# frontend_v2.net
KiCad netlist of a schematic drawn in EAGLE
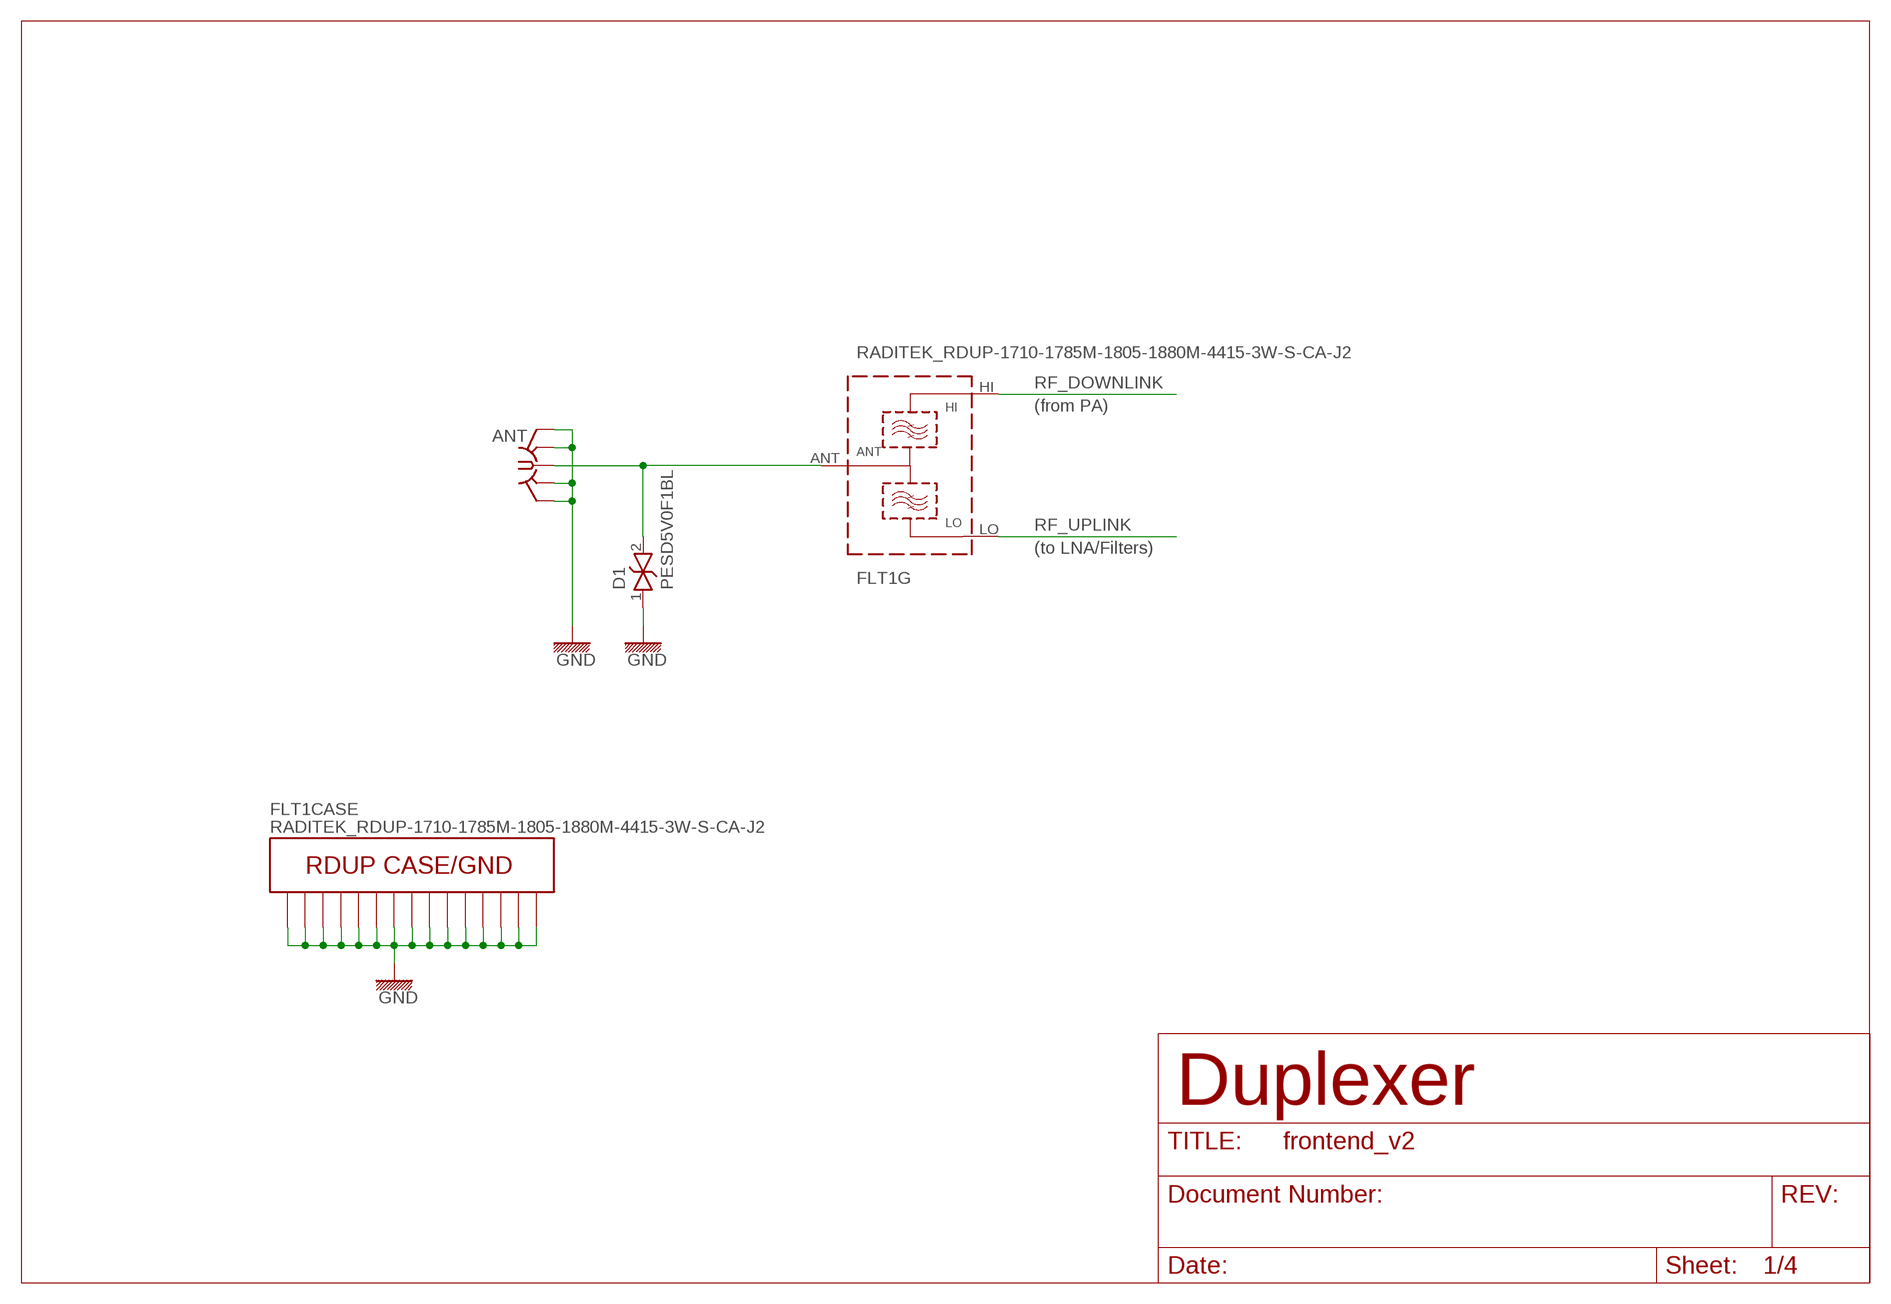
[diagram p0: schematic, sheet 1]
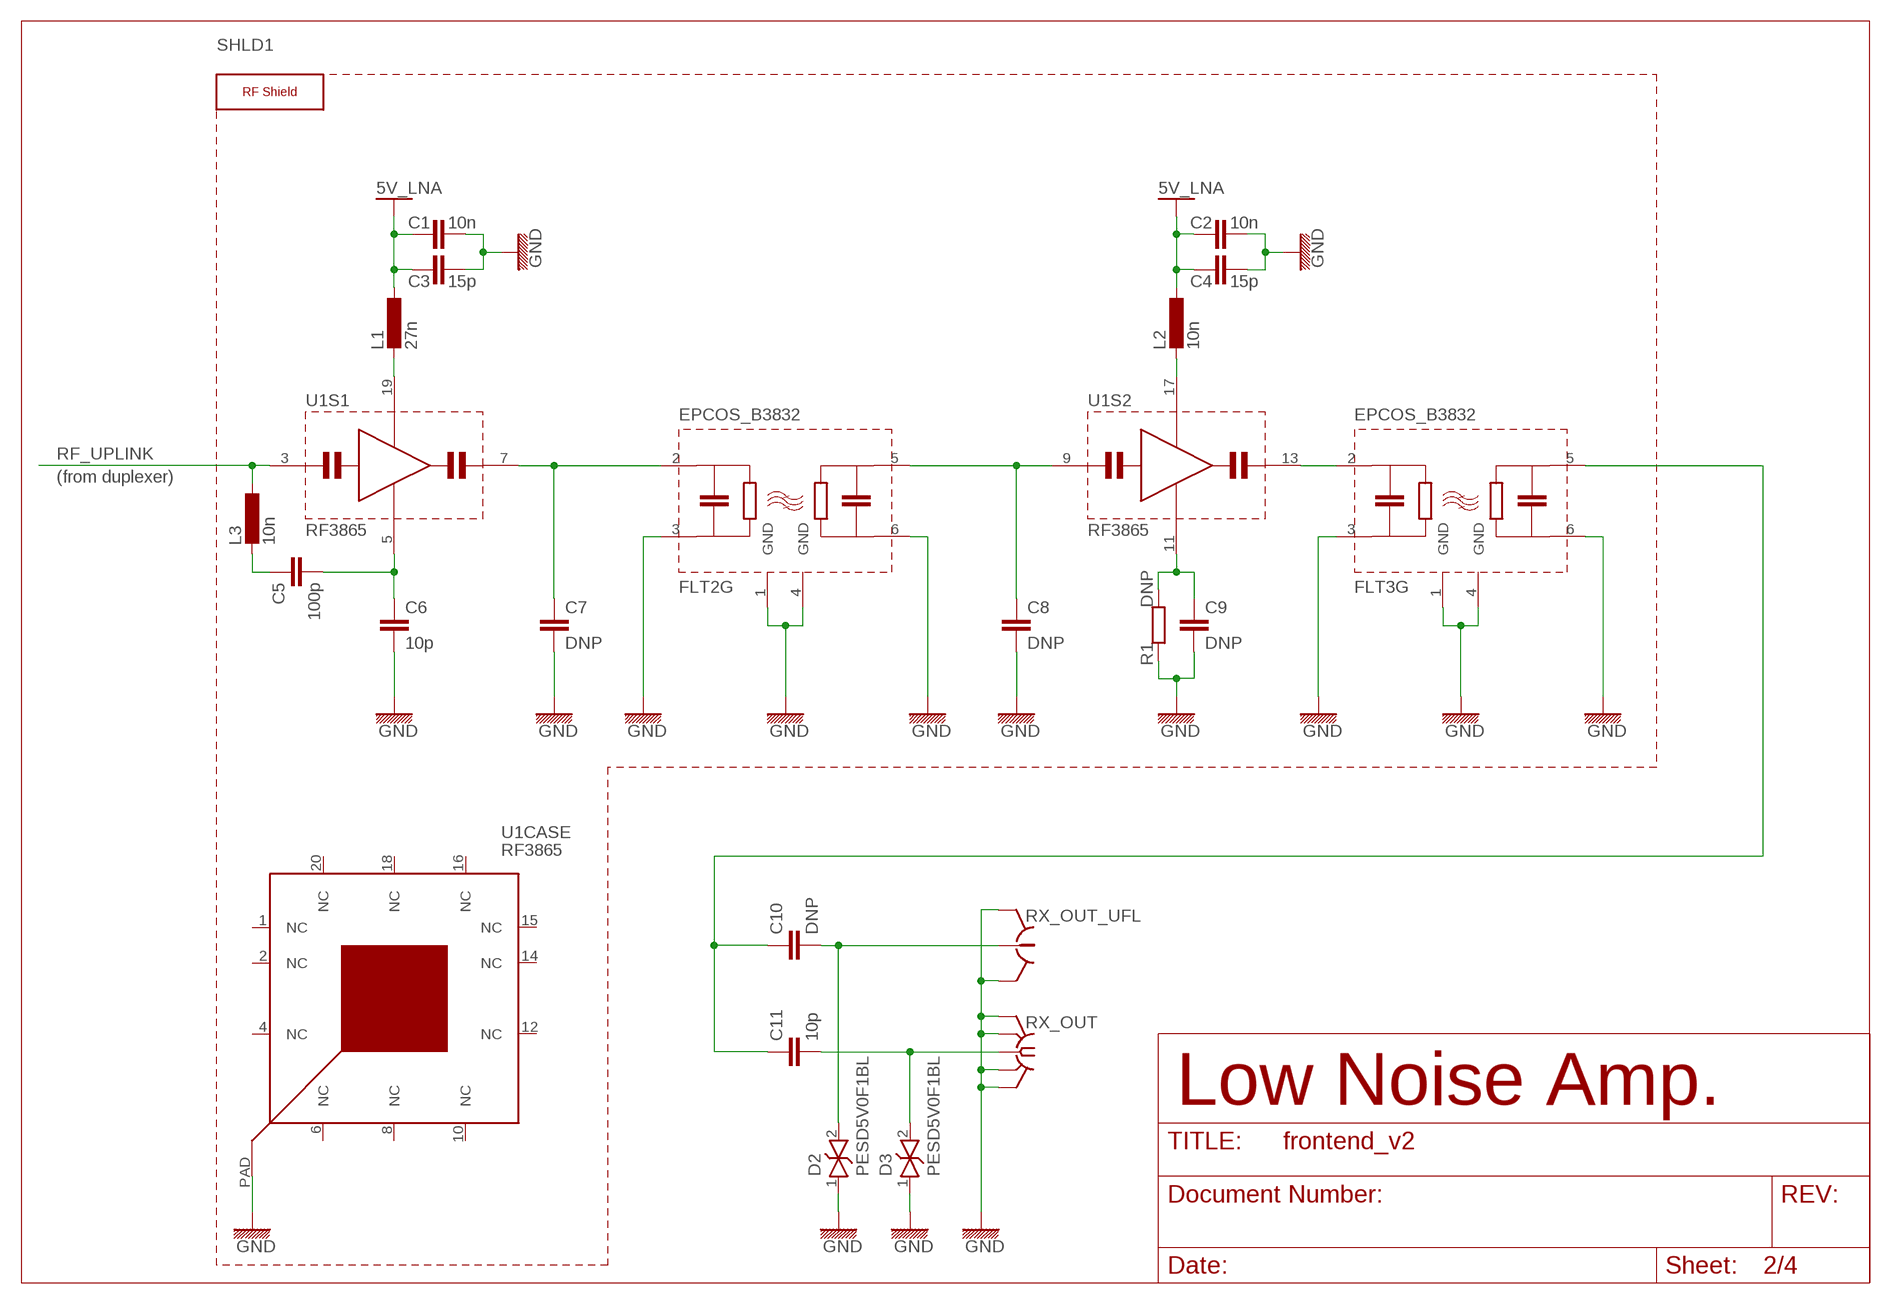
[diagram p1: schematic, sheet 2]
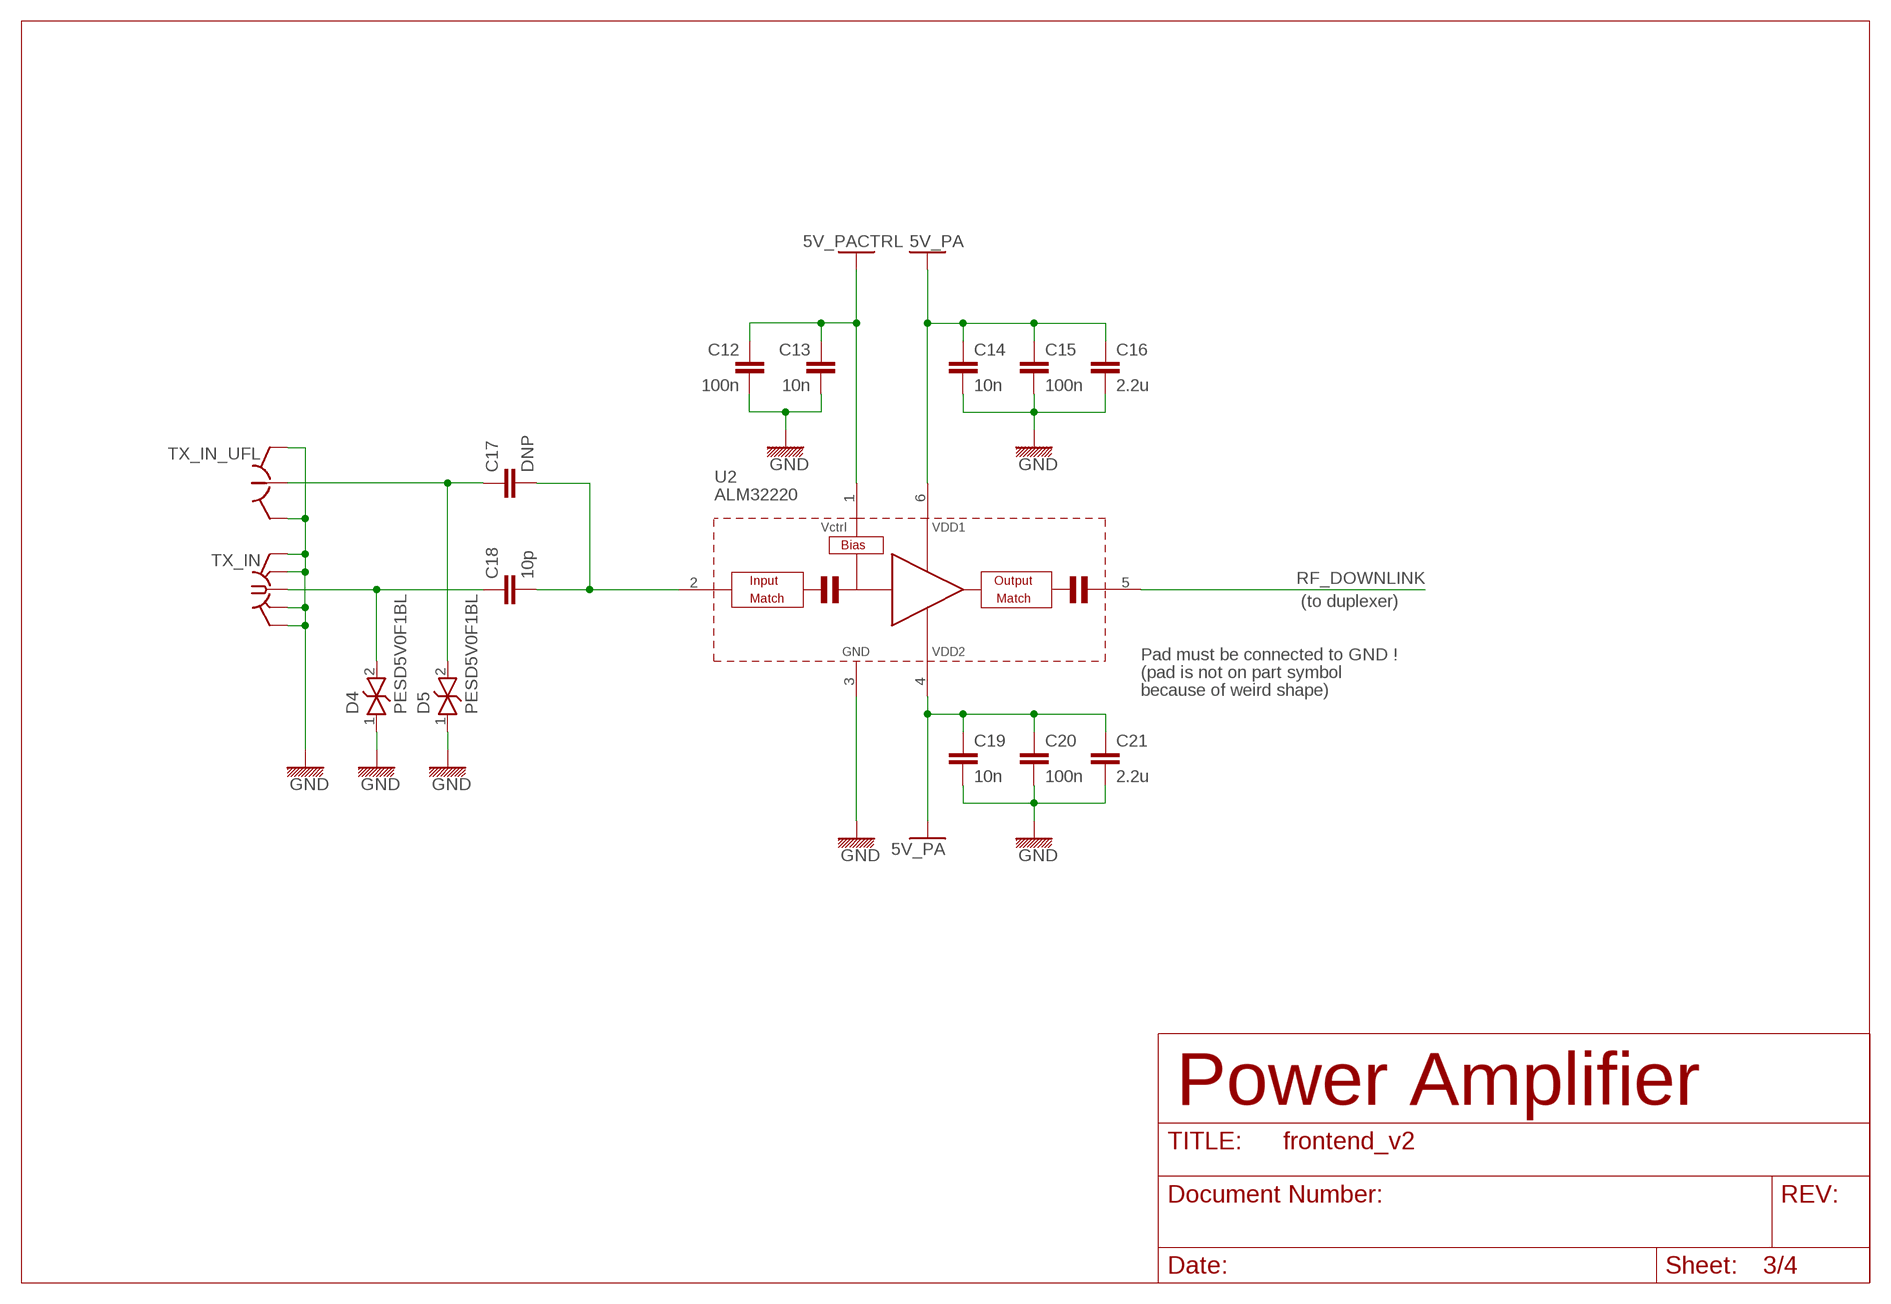
[diagram p2: schematic, sheet 3]
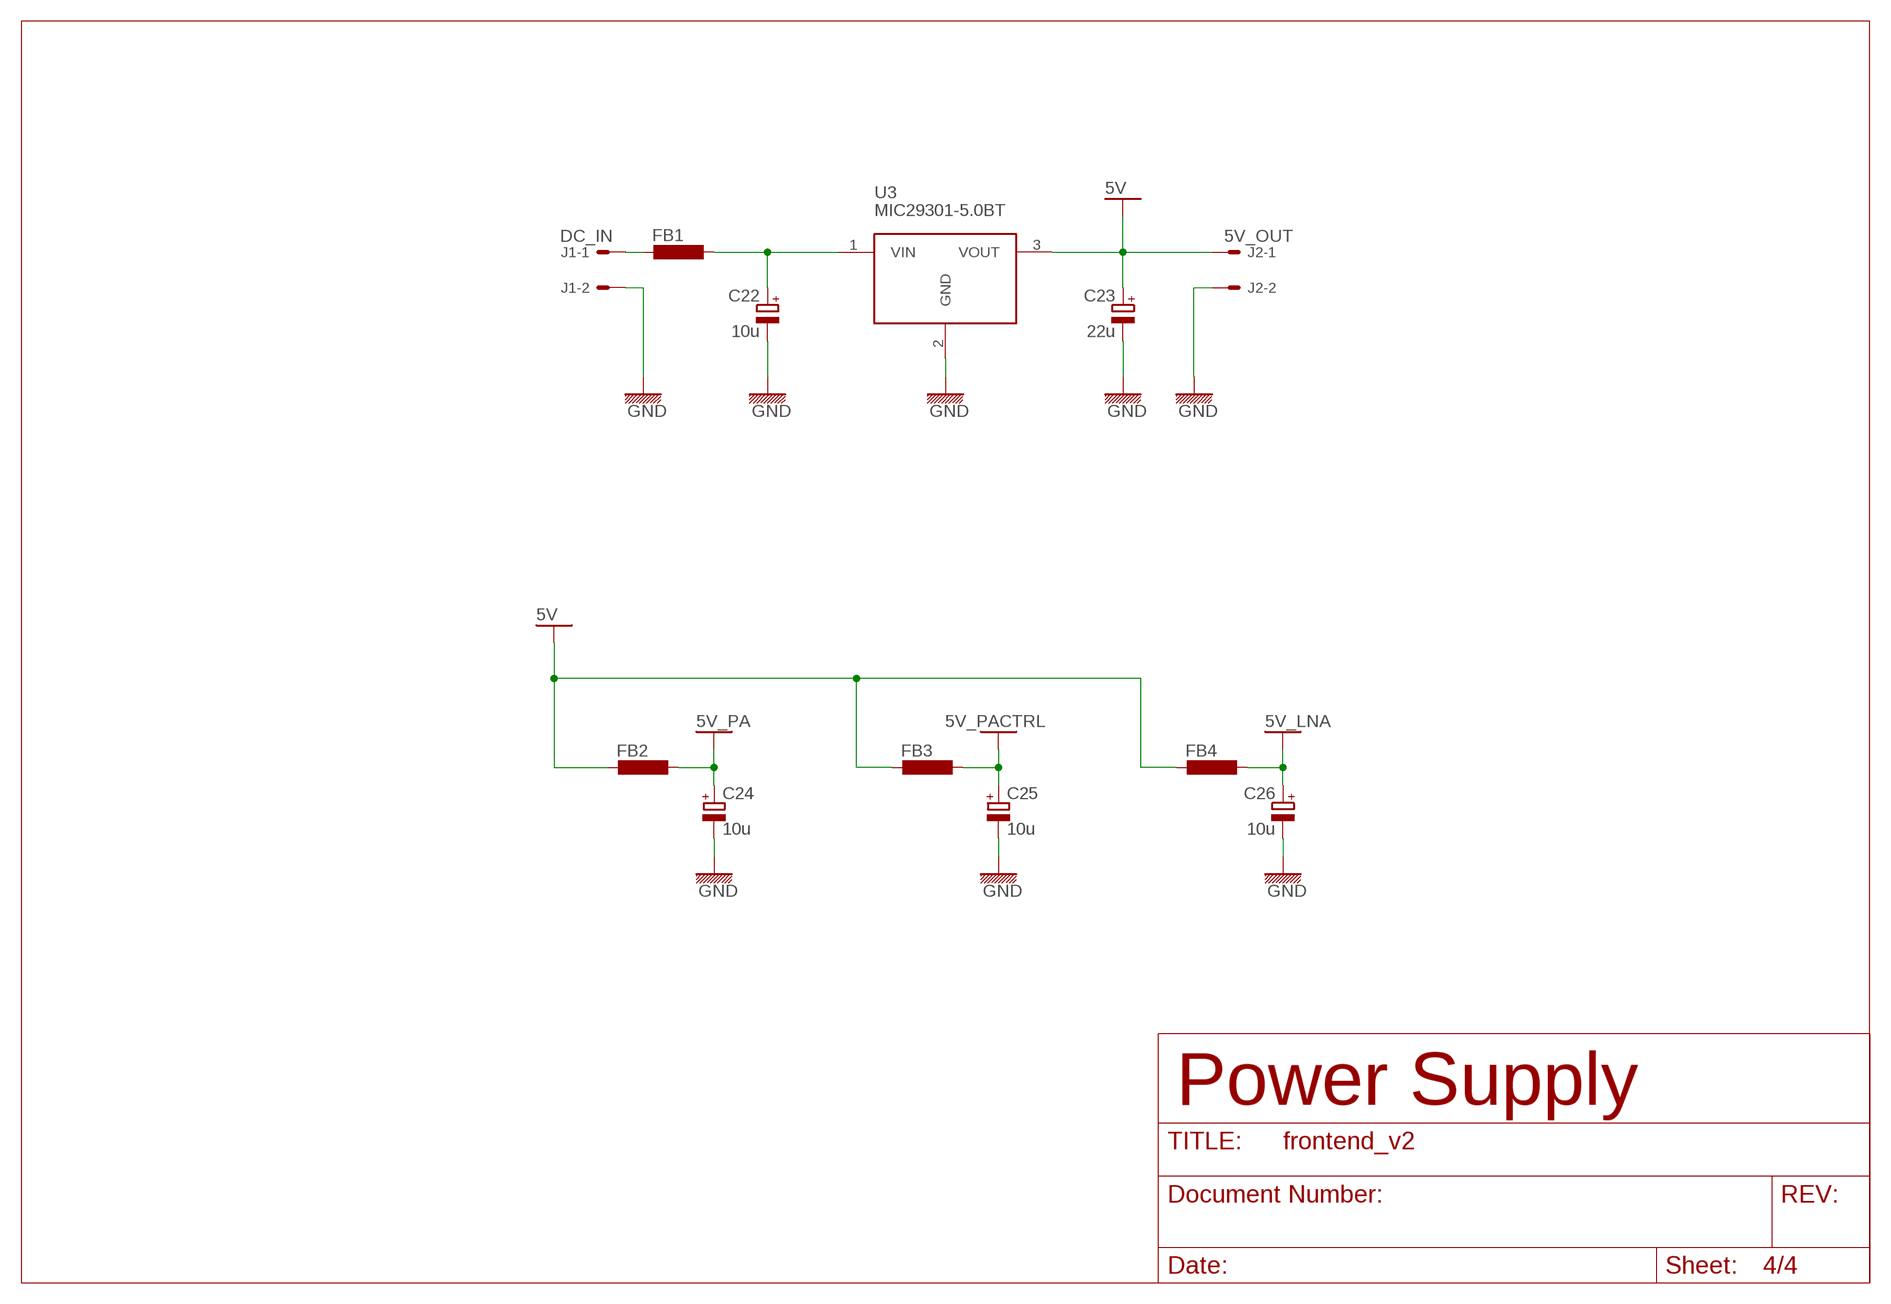
[diagram p3: schematic, sheet 4]

(export (version "E")
  (design (tool "Eeschema 10.0.6"))
  (components
    (comp (ref "C1")
      (value "10n")
      (footprint "eagle-import:0603")
      (libsource (lib "eagle-import") (part "C-EU_0603"))
    )
    (comp (ref "C2")
      (value "10n")
      (footprint "eagle-import:0603")
      (libsource (lib "eagle-import") (part "C-EU_0603"))
    )
    (comp (ref "C3")
      (value "15p")
      (footprint "eagle-import:0603")
      (libsource (lib "eagle-import") (part "C-EU_0603"))
    )
    (comp (ref "C4")
      (value "15p")
      (footprint "eagle-import:0603")
      (libsource (lib "eagle-import") (part "C-EU_0603"))
    )
    (comp (ref "C5")
      (value "100p")
      (footprint "eagle-import:0603")
      (libsource (lib "eagle-import") (part "C-EU_0603"))
    )
    (comp (ref "C6")
      (value "10p")
      (footprint "eagle-import:0603")
      (libsource (lib "eagle-import") (part "C-EU_0603"))
    )
    (comp (ref "C7")
      (value "DNP")
      (footprint "eagle-import:0603")
      (libsource (lib "eagle-import") (part "C-EU_0603"))
    )
    (comp (ref "C8")
      (value "DNP")
      (footprint "eagle-import:0603")
      (libsource (lib "eagle-import") (part "C-EU_0603"))
    )
    (comp (ref "C9")
      (value "DNP")
      (footprint "eagle-import:0603")
      (libsource (lib "eagle-import") (part "C-EU_0603"))
    )
    (comp (ref "C10")
      (value "DNP")
      (footprint "eagle-import:0603")
      (libsource (lib "eagle-import") (part "C-EU_0603"))
    )
    (comp (ref "C11")
      (value "10p")
      (footprint "eagle-import:0603")
      (libsource (lib "eagle-import") (part "C-EU_0603"))
    )
    (comp (ref "D2")
      (value "PESD5V0F1BL")
      (footprint "eagle-import:SOD882")
      (libsource (lib "eagle-import") (part "D_ESD_SOD882"))
    )
    (comp (ref "D3")
      (value "PESD5V0F1BL")
      (footprint "eagle-import:SOD882")
      (libsource (lib "eagle-import") (part "D_ESD_SOD882"))
    )
    (comp (ref "FLT2")
      (value "EPCOS_B3832")
      (footprint "eagle-import:DCC6C")
      (libsource (lib "eagle-import") (part "EPCOS_B3832"))
    )
    (comp (ref "FLT3")
      (value "EPCOS_B3832")
      (footprint "eagle-import:DCC6C")
      (libsource (lib "eagle-import") (part "EPCOS_B3832"))
    )
    (comp (ref "L1")
      (value "27n")
      (footprint "eagle-import:0603")
      (libsource (lib "eagle-import") (part "L-EU_0603"))
    )
    (comp (ref "L2")
      (value "10n")
      (footprint "eagle-import:0603")
      (libsource (lib "eagle-import") (part "L-EU_0603"))
    )
    (comp (ref "L3")
      (value "10n")
      (footprint "eagle-import:0603")
      (libsource (lib "eagle-import") (part "L-EU_0603"))
    )
    (comp (ref "R1")
      (value "DNP")
      (footprint "eagle-import:0603")
      (libsource (lib "eagle-import") (part "R-EU_0603"))
    )
    (comp (ref "RX_OUT")
      (value "SMA-F-S-TH")
      (footprint "eagle-import:SMA-F-S-TH")
      (libsource (lib "eagle-import") (part "SMA-F-S-TH"))
    )
    (comp (ref "RX_OUT_UFL")
      (value "HRS_UFL")
      (footprint "eagle-import:HRS_UFL")
      (libsource (lib "eagle-import") (part "HRS_UFL"))
    )
    (comp (ref "SHLD1")
      (value "SHIELD25X25")
      (footprint "eagle-import:WE-SHC-SMD_25X25")
      (libsource (lib "eagle-import") (part "SHIELD25X25"))
    )
    (comp (ref "U1")
      (value "RF3865")
      (footprint "eagle-import:QFN20_5X5_PAD")
      (libsource (lib "eagle-import") (part "RF3865"))
    )
    (comp (ref "C12")
      (value "100n")
      (footprint "eagle-import:0603")
      (libsource (lib "eagle-import") (part "C-EU_0603"))
    )
    (comp (ref "C13")
      (value "10n")
      (footprint "eagle-import:0603")
      (libsource (lib "eagle-import") (part "C-EU_0603"))
    )
    (comp (ref "C14")
      (value "10n")
      (footprint "eagle-import:0603")
      (libsource (lib "eagle-import") (part "C-EU_0603"))
    )
    (comp (ref "C15")
      (value "100n")
      (footprint "eagle-import:0603")
      (libsource (lib "eagle-import") (part "C-EU_0603"))
    )
    (comp (ref "C16")
      (value "2.2u")
      (footprint "eagle-import:0805")
      (libsource (lib "eagle-import") (part "C-EU_0805"))
    )
    (comp (ref "C17")
      (value "DNP")
      (footprint "eagle-import:0603")
      (libsource (lib "eagle-import") (part "C-EU_0603"))
    )
    (comp (ref "C18")
      (value "10p")
      (footprint "eagle-import:0603")
      (libsource (lib "eagle-import") (part "C-EU_0603"))
    )
    (comp (ref "C19")
      (value "10n")
      (footprint "eagle-import:0603")
      (libsource (lib "eagle-import") (part "C-EU_0603"))
    )
    (comp (ref "C20")
      (value "100n")
      (footprint "eagle-import:0603")
      (libsource (lib "eagle-import") (part "C-EU_0603"))
    )
    (comp (ref "C21")
      (value "2.2u")
      (footprint "eagle-import:0805")
      (libsource (lib "eagle-import") (part "C-EU_0805"))
    )
    (comp (ref "D4")
      (value "PESD5V0F1BL")
      (footprint "eagle-import:SOD882")
      (libsource (lib "eagle-import") (part "D_ESD_SOD882"))
    )
    (comp (ref "D5")
      (value "PESD5V0F1BL")
      (footprint "eagle-import:SOD882")
      (libsource (lib "eagle-import") (part "D_ESD_SOD882"))
    )
    (comp (ref "TX_IN")
      (value "SMA-F-S-TH")
      (footprint "eagle-import:SMA-F-S-TH")
      (libsource (lib "eagle-import") (part "SMA-F-S-TH"))
    )
    (comp (ref "TX_IN_UFL")
      (value "HRS_UFL")
      (footprint "eagle-import:HRS_UFL")
      (libsource (lib "eagle-import") (part "HRS_UFL"))
    )
    (comp (ref "U2")
      (value "ALM32220")
      (footprint "eagle-import:ALM32X20")
      (libsource (lib "eagle-import") (part "ALM32220"))
    )
    (comp (ref "C22")
      (value "10u")
      (footprint "eagle-import:SMC_A")
      (libsource (lib "eagle-import") (part "CPOL-EUSMCA"))
    )
    (comp (ref "C23")
      (value "22u")
      (footprint "eagle-import:SMC_A")
      (libsource (lib "eagle-import") (part "CPOL-EUSMCA"))
    )
    (comp (ref "C24")
      (value "10u")
      (footprint "eagle-import:SMC_A")
      (libsource (lib "eagle-import") (part "CPOL-EUSMCA"))
    )
    (comp (ref "C25")
      (value "10u")
      (footprint "eagle-import:SMC_A")
      (libsource (lib "eagle-import") (part "CPOL-EUSMCA"))
    )
    (comp (ref "C26")
      (value "10u")
      (footprint "eagle-import:SMC_A")
      (libsource (lib "eagle-import") (part "CPOL-EUSMCA"))
    )
    (comp (ref "FB1")
      (value "FBEAD_1206")
      (footprint "eagle-import:1206")
      (libsource (lib "eagle-import") (part "FBEAD_1206"))
    )
    (comp (ref "FB2")
      (value "FBEAD_1206")
      (footprint "eagle-import:1206")
      (libsource (lib "eagle-import") (part "FBEAD_1206"))
    )
    (comp (ref "FB3")
      (value "FBEAD_0603")
      (footprint "eagle-import:0603")
      (libsource (lib "eagle-import") (part "FBEAD_0603"))
    )
    (comp (ref "FB4")
      (value "FBEAD_0603")
      (footprint "eagle-import:0603")
      (libsource (lib "eagle-import") (part "FBEAD_0603"))
    )
    (comp (ref "J1")
      (value "DC_IN")
      (footprint "eagle-import:6410-02")
      (libsource (lib "eagle-import") (part "22-?-0227-2021"))
    )
    (comp (ref "J2")
      (value "5V_OUT")
      (footprint "eagle-import:6410-02")
      (fields (field (name "OC_FARNELL") "unknown") (field (name "OC_NEWARK") "unknown"))
      (libsource (lib "eagle-import") (part "22-?-0227-2021"))
    )
    (comp (ref "U3")
      (value "MIC29301-5.0BT")
      (footprint "eagle-import:TO220BV")
      (libsource (lib "eagle-import") (part "MIC29XXX-FIX_WT_TO220BV"))
    )
    (comp (ref "ANT")
      (value "SMA-F-S-TH")
      (footprint "eagle-import:SMA-F-S-TH")
      (libsource (lib "eagle-import") (part "SMA-F-S-TH"))
    )
    (comp (ref "D1")
      (value "PESD5V0F1BL")
      (footprint "eagle-import:SOD882")
      (libsource (lib "eagle-import") (part "D_ESD_SOD882"))
    )
    (comp (ref "FLT1")
      (value "RADITEK_RDUP-1710-1785M-1805-1880M-4415-3W-S-CA-J2")
      (footprint "eagle-import:RADITEK_RDUP_4415")
      (libsource (lib "eagle-import") (part "RADITEK_RDUP-1710-1785M-1805-1880M-4415-3W-S-CA-J2"))
    )
  )
  (nets
    (net (code "1") (name "5V") (class "Default")
      (node (ref "C23") (pin "+") (pinfunction "+_+") (pintype "passive"))
      (node (ref "FB2") (pin "1") (pinfunction "1_1") (pintype "passive"))
      (node (ref "FB3") (pin "1") (pinfunction "1_1") (pintype "passive"))
      (node (ref "FB4") (pin "1") (pinfunction "1_1") (pintype "passive"))
      (node (ref "J2") (pin "1") (pinfunction "S_1") (pintype "passive"))
      (node (ref "U3") (pin "3") (pinfunction "VOUT_3") (pintype "power_in"))
    )
    (net (code "2") (name "5V_LNA") (class "Default")
      (node (ref "C1") (pin "1") (pinfunction "1_1") (pintype "passive"))
      (node (ref "C2") (pin "1") (pinfunction "1_1") (pintype "passive"))
      (node (ref "C26") (pin "+") (pinfunction "+_+") (pintype "passive"))
      (node (ref "C3") (pin "1") (pinfunction "1_1") (pintype "passive"))
      (node (ref "C4") (pin "1") (pinfunction "1_1") (pintype "passive"))
      (node (ref "FB4") (pin "2") (pinfunction "2_2") (pintype "passive"))
      (node (ref "L1") (pin "1") (pinfunction "1_1") (pintype "passive"))
      (node (ref "L2") (pin "1") (pinfunction "1_1") (pintype "passive"))
    )
    (net (code "3") (name "5V_PA") (class "Default")
      (node (ref "C14") (pin "1") (pinfunction "1_1") (pintype "passive"))
      (node (ref "C15") (pin "1") (pinfunction "1_1") (pintype "passive"))
      (node (ref "C16") (pin "1") (pinfunction "1_1") (pintype "passive"))
      (node (ref "C19") (pin "1") (pinfunction "1_1") (pintype "passive"))
      (node (ref "C20") (pin "1") (pinfunction "1_1") (pintype "passive"))
      (node (ref "C21") (pin "1") (pinfunction "1_1") (pintype "passive"))
      (node (ref "C24") (pin "+") (pinfunction "+_+") (pintype "passive"))
      (node (ref "FB2") (pin "2") (pinfunction "2_2") (pintype "passive"))
      (node (ref "U2") (pin "4") (pinfunction "VDD2_4") (pintype "power_in"))
      (node (ref "U2") (pin "6") (pinfunction "VDD1_6") (pintype "power_in"))
    )
    (net (code "4") (name "5V_PACTRL") (class "Default")
      (node (ref "C12") (pin "1") (pinfunction "1_1") (pintype "passive"))
      (node (ref "C13") (pin "1") (pinfunction "1_1") (pintype "passive"))
      (node (ref "C25") (pin "+") (pinfunction "+_+") (pintype "passive"))
      (node (ref "FB3") (pin "2") (pinfunction "2_2") (pintype "passive"))
      (node (ref "U2") (pin "1") (pinfunction "VCTRL_1") (pintype "power_in"))
    )
    (net (code "5") (name "GND") (class "Default")
      (node (ref "ANT") (pin "G1") (pinfunction "GND_G1") (pintype "power_in"))
      (node (ref "ANT") (pin "G2") (pinfunction "GND_G2") (pintype "power_in"))
      (node (ref "ANT") (pin "G3") (pinfunction "GND_G3") (pintype "power_in"))
      (node (ref "ANT") (pin "G4") (pinfunction "GND_G4") (pintype "power_in"))
      (node (ref "C1") (pin "2") (pinfunction "2_2") (pintype "passive"))
      (node (ref "C12") (pin "2") (pinfunction "2_2") (pintype "passive"))
      (node (ref "C13") (pin "2") (pinfunction "2_2") (pintype "passive"))
      (node (ref "C14") (pin "2") (pinfunction "2_2") (pintype "passive"))
      (node (ref "C15") (pin "2") (pinfunction "2_2") (pintype "passive"))
      (node (ref "C16") (pin "2") (pinfunction "2_2") (pintype "passive"))
      (node (ref "C19") (pin "2") (pinfunction "2_2") (pintype "passive"))
      (node (ref "C2") (pin "2") (pinfunction "2_2") (pintype "passive"))
      (node (ref "C20") (pin "2") (pinfunction "2_2") (pintype "passive"))
      (node (ref "C21") (pin "2") (pinfunction "2_2") (pintype "passive"))
      (node (ref "C22") (pin "-") (pinfunction "-_-") (pintype "passive"))
      (node (ref "C23") (pin "-") (pinfunction "-_-") (pintype "passive"))
      (node (ref "C24") (pin "-") (pinfunction "-_-") (pintype "passive"))
      (node (ref "C25") (pin "-") (pinfunction "-_-") (pintype "passive"))
      (node (ref "C26") (pin "-") (pinfunction "-_-") (pintype "passive"))
      (node (ref "C3") (pin "2") (pinfunction "2_2") (pintype "passive"))
      (node (ref "C4") (pin "2") (pinfunction "2_2") (pintype "passive"))
      (node (ref "C6") (pin "2") (pinfunction "2_2") (pintype "passive"))
      (node (ref "C7") (pin "2") (pinfunction "2_2") (pintype "passive"))
      (node (ref "C8") (pin "2") (pinfunction "2_2") (pintype "passive"))
      (node (ref "C9") (pin "2") (pinfunction "2_2") (pintype "passive"))
      (node (ref "D1") (pin "1") (pinfunction "1_1") (pintype "passive"))
      (node (ref "D2") (pin "1") (pinfunction "1_1") (pintype "passive"))
      (node (ref "D3") (pin "1") (pinfunction "1_1") (pintype "passive"))
      (node (ref "D4") (pin "1") (pinfunction "1_1") (pintype "passive"))
      (node (ref "D5") (pin "1") (pinfunction "1_1") (pintype "passive"))
      (node (ref "FLT1") (pin "GND@1") (pinfunction "GND_GND@1") (pintype "power_in"))
      (node (ref "FLT1") (pin "GND@10") (pinfunction "GND_GND@10") (pintype "power_in"))
      (node (ref "FLT1") (pin "GND@11") (pinfunction "GND_GND@11") (pintype "power_in"))
      (node (ref "FLT1") (pin "GND@12") (pinfunction "GND_GND@12") (pintype "power_in"))
      (node (ref "FLT1") (pin "GND@13") (pinfunction "GND_GND@13") (pintype "power_in"))
      (node (ref "FLT1") (pin "GND@14") (pinfunction "GND_GND@14") (pintype "power_in"))
      (node (ref "FLT1") (pin "GND@15") (pinfunction "GND_GND@15") (pintype "power_in"))
      (node (ref "FLT1") (pin "GND@2") (pinfunction "GND_GND@2") (pintype "power_in"))
      (node (ref "FLT1") (pin "GND@3") (pinfunction "GND_GND@3") (pintype "power_in"))
      (node (ref "FLT1") (pin "GND@4") (pinfunction "GND_GND@4") (pintype "power_in"))
      (node (ref "FLT1") (pin "GND@5") (pinfunction "GND_GND@5") (pintype "power_in"))
      (node (ref "FLT1") (pin "GND@6") (pinfunction "GND_GND@6") (pintype "power_in"))
      (node (ref "FLT1") (pin "GND@7") (pinfunction "GND_GND@7") (pintype "power_in"))
      (node (ref "FLT1") (pin "GND@8") (pinfunction "GND_GND@8") (pintype "power_in"))
      (node (ref "FLT1") (pin "GND@9") (pinfunction "GND_GND@9") (pintype "power_in"))
      (node (ref "FLT2") (pin "1") (pinfunction "GND_1") (pintype "power_in"))
      (node (ref "FLT2") (pin "3") (pinfunction "IN_GND_3") (pintype "passive"))
      (node (ref "FLT2") (pin "4") (pinfunction "GND_4") (pintype "power_in"))
      (node (ref "FLT2") (pin "6") (pinfunction "OUT_GND_6") (pintype "passive"))
      (node (ref "FLT3") (pin "1") (pinfunction "GND_1") (pintype "power_in"))
      (node (ref "FLT3") (pin "3") (pinfunction "IN_GND_3") (pintype "passive"))
      (node (ref "FLT3") (pin "4") (pinfunction "GND_4") (pintype "power_in"))
      (node (ref "FLT3") (pin "6") (pinfunction "OUT_GND_6") (pintype "passive"))
      (node (ref "J1") (pin "2") (pinfunction "S_2") (pintype "passive"))
      (node (ref "J2") (pin "2") (pinfunction "S_2") (pintype "passive"))
      (node (ref "R1") (pin "1") (pinfunction "1_1") (pintype "passive"))
      (node (ref "RX_OUT") (pin "G1") (pinfunction "GND_G1") (pintype "power_in"))
      (node (ref "RX_OUT") (pin "G2") (pinfunction "GND_G2") (pintype "power_in"))
      (node (ref "RX_OUT") (pin "G3") (pinfunction "GND_G3") (pintype "power_in"))
      (node (ref "RX_OUT") (pin "G4") (pinfunction "GND_G4") (pintype "power_in"))
      (node (ref "RX_OUT_UFL") (pin "GND@1") (pinfunction "GND_GND@1") (pintype "power_in"))
      (node (ref "RX_OUT_UFL") (pin "GND@2") (pinfunction "GND_GND@2") (pintype "power_in"))
      (node (ref "TX_IN") (pin "G1") (pinfunction "GND_G1") (pintype "power_in"))
      (node (ref "TX_IN") (pin "G2") (pinfunction "GND_G2") (pintype "power_in"))
      (node (ref "TX_IN") (pin "G3") (pinfunction "GND_G3") (pintype "power_in"))
      (node (ref "TX_IN") (pin "G4") (pinfunction "GND_G4") (pintype "power_in"))
      (node (ref "TX_IN_UFL") (pin "GND@1") (pinfunction "GND_GND@1") (pintype "power_in"))
      (node (ref "TX_IN_UFL") (pin "GND@2") (pinfunction "GND_GND@2") (pintype "power_in"))
      (node (ref "U1") (pin "PAD") (pinfunction "CASE_GND_PAD") (pintype "power_in"))
      (node (ref "U2") (pin "3") (pinfunction "GND_3") (pintype "power_in"))
      (node (ref "U3") (pin "2") (pinfunction "GND_2") (pintype "power_in"))
    )
    (net (code "6") (name "Net-(ANT-1)") (class "Default")
      (node (ref "ANT") (pin "C") (pinfunction "1_C") (pintype "passive"))
      (node (ref "D1") (pin "2") (pinfunction "2_2") (pintype "passive"))
      (node (ref "FLT1") (pin "ANT") (pinfunction "ANT_ANT") (pintype "passive"))
    )
    (net (code "7") (name "Net-(C5-Pad1)") (class "Default")
      (node (ref "C5") (pin "1") (pinfunction "1_1") (pintype "passive"))
      (node (ref "L3") (pin "2") (pinfunction "2_2") (pintype "passive"))
    )
    (net (code "8") (name "Net-(FLT2B-IN)") (class "Default")
      (node (ref "C7") (pin "1") (pinfunction "1_1") (pintype "passive"))
      (node (ref "FLT2") (pin "2") (pinfunction "IN_2") (pintype "passive"))
      (node (ref "U1") (pin "7") (pinfunction "RF_OUT_7") (pintype "bidirectional"))
    )
    (net (code "9") (name "Net-(FLT2B-OUT)") (class "Default")
      (node (ref "C8") (pin "1") (pinfunction "1_1") (pintype "passive"))
      (node (ref "FLT2") (pin "5") (pinfunction "OUT_5") (pintype "passive"))
      (node (ref "U1") (pin "9") (pinfunction "RF_IN_9") (pintype "bidirectional"))
    )
    (net (code "10") (name "Net-(FLT3B-IN)") (class "Default")
      (node (ref "FLT3") (pin "2") (pinfunction "IN_2") (pintype "passive"))
      (node (ref "U1") (pin "13") (pinfunction "RF_OUT_13") (pintype "bidirectional"))
    )
    (net (code "11") (name "Net-(FLT3B-OUT)") (class "Default")
      (node (ref "C10") (pin "1") (pinfunction "1_1") (pintype "passive"))
      (node (ref "C11") (pin "1") (pinfunction "1_1") (pintype "passive"))
      (node (ref "FLT3") (pin "5") (pinfunction "OUT_5") (pintype "passive"))
    )
    (net (code "12") (name "Net-(J1A-S)") (class "Default")
      (node (ref "FB1") (pin "1") (pinfunction "1_1") (pintype "passive"))
      (node (ref "J1") (pin "1") (pinfunction "S_1") (pintype "passive"))
    )
    (net (code "13") (name "Net-(RX_OUT-1)") (class "Default")
      (node (ref "C11") (pin "2") (pinfunction "2_2") (pintype "passive"))
      (node (ref "D3") (pin "2") (pinfunction "2_2") (pintype "passive"))
      (node (ref "RX_OUT") (pin "C") (pinfunction "1_C") (pintype "passive"))
    )
    (net (code "14") (name "Net-(RX_OUT_UFL-1)") (class "Default")
      (node (ref "C10") (pin "2") (pinfunction "2_2") (pintype "passive"))
      (node (ref "D2") (pin "2") (pinfunction "2_2") (pintype "passive"))
      (node (ref "RX_OUT_UFL") (pin "SIG") (pinfunction "1_SIG") (pintype "passive"))
    )
    (net (code "15") (name "Net-(TX_IN-1)") (class "Default")
      (node (ref "C18") (pin "1") (pinfunction "1_1") (pintype "passive"))
      (node (ref "D4") (pin "2") (pinfunction "2_2") (pintype "passive"))
      (node (ref "TX_IN") (pin "C") (pinfunction "1_C") (pintype "passive"))
    )
    (net (code "16") (name "Net-(TX_IN_UFL-1)") (class "Default")
      (node (ref "C17") (pin "1") (pinfunction "1_1") (pintype "passive"))
      (node (ref "D5") (pin "2") (pinfunction "2_2") (pintype "passive"))
      (node (ref "TX_IN_UFL") (pin "SIG") (pinfunction "1_SIG") (pintype "passive"))
    )
    (net (code "17") (name "Net-(U1B-AC_GND)") (class "Default")
      (node (ref "C5") (pin "2") (pinfunction "2_2") (pintype "passive"))
      (node (ref "C6") (pin "1") (pinfunction "1_1") (pintype "passive"))
      (node (ref "U1") (pin "5") (pinfunction "AC_GND_5") (pintype "bidirectional"))
    )
    (net (code "18") (name "Net-(U1B-VDD)") (class "Default")
      (node (ref "L1") (pin "2") (pinfunction "2_2") (pintype "passive"))
      (node (ref "U1") (pin "19") (pinfunction "VDD_19") (pintype "bidirectional"))
    )
    (net (code "19") (name "Net-(U1C-AC_GND)") (class "Default")
      (node (ref "C9") (pin "1") (pinfunction "1_1") (pintype "passive"))
      (node (ref "R1") (pin "2") (pinfunction "2_2") (pintype "passive"))
      (node (ref "U1") (pin "11") (pinfunction "AC_GND_11") (pintype "bidirectional"))
    )
    (net (code "20") (name "Net-(U1C-VDD)") (class "Default")
      (node (ref "L2") (pin "2") (pinfunction "2_2") (pintype "passive"))
      (node (ref "U1") (pin "17") (pinfunction "VDD_17") (pintype "bidirectional"))
    )
    (net (code "21") (name "Net-(U2-RF_IN)") (class "Default")
      (node (ref "C17") (pin "2") (pinfunction "2_2") (pintype "passive"))
      (node (ref "C18") (pin "2") (pinfunction "2_2") (pintype "passive"))
      (node (ref "U2") (pin "2") (pinfunction "RF_IN_2") (pintype "input"))
    )
    (net (code "22") (name "Net-(U3-VIN)") (class "Default")
      (node (ref "C22") (pin "+") (pinfunction "+_+") (pintype "passive"))
      (node (ref "FB1") (pin "2") (pinfunction "2_2") (pintype "passive"))
      (node (ref "U3") (pin "1") (pinfunction "VIN_1") (pintype "power_in"))
    )
    (net (code "23") (name "RF_DOWNLINK") (class "Default")
      (node (ref "FLT1") (pin "HI") (pinfunction "HI_HI") (pintype "passive"))
      (node (ref "U2") (pin "5") (pinfunction "RF_OUT_5") (pintype "output"))
    )
    (net (code "24") (name "RF_UPLINK") (class "Default")
      (node (ref "FLT1") (pin "LO") (pinfunction "LO_LO") (pintype "passive"))
      (node (ref "L3") (pin "1") (pinfunction "1_1") (pintype "passive"))
      (node (ref "U1") (pin "3") (pinfunction "RF_IN_3") (pintype "bidirectional"))
    )
    (net (code "25") (name "unconnected-(U1A-NC-Pad1)") (class "Default")
      (node (ref "U1") (pin "1") (pinfunction "NC_1") (pintype "no_connect"))
    )
    (net (code "26") (name "unconnected-(U1A-NC-Pad2)") (class "Default")
      (node (ref "U1") (pin "2") (pinfunction "NC_2") (pintype "no_connect"))
    )
    (net (code "27") (name "unconnected-(U1A-NC-Pad4)") (class "Default")
      (node (ref "U1") (pin "4") (pinfunction "NC_4") (pintype "no_connect"))
    )
    (net (code "28") (name "unconnected-(U1A-NC-Pad6)") (class "Default")
      (node (ref "U1") (pin "6") (pinfunction "NC_6") (pintype "no_connect"))
    )
    (net (code "29") (name "unconnected-(U1A-NC-Pad8)") (class "Default")
      (node (ref "U1") (pin "8") (pinfunction "NC_8") (pintype "no_connect"))
    )
    (net (code "30") (name "unconnected-(U1A-NC-Pad10)") (class "Default")
      (node (ref "U1") (pin "10") (pinfunction "NC_10") (pintype "no_connect"))
    )
    (net (code "31") (name "unconnected-(U1A-NC-Pad12)") (class "Default")
      (node (ref "U1") (pin "12") (pinfunction "NC_12") (pintype "no_connect"))
    )
    (net (code "32") (name "unconnected-(U1A-NC-Pad14)") (class "Default")
      (node (ref "U1") (pin "14") (pinfunction "NC_14") (pintype "no_connect"))
    )
    (net (code "33") (name "unconnected-(U1A-NC-Pad15)") (class "Default")
      (node (ref "U1") (pin "15") (pinfunction "NC_15") (pintype "no_connect"))
    )
    (net (code "34") (name "unconnected-(U1A-NC-Pad16)") (class "Default")
      (node (ref "U1") (pin "16") (pinfunction "NC_16") (pintype "no_connect"))
    )
    (net (code "35") (name "unconnected-(U1A-NC-Pad18)") (class "Default")
      (node (ref "U1") (pin "18") (pinfunction "NC_18") (pintype "no_connect"))
    )
    (net (code "36") (name "unconnected-(U1A-NC-Pad20)") (class "Default")
      (node (ref "U1") (pin "20") (pinfunction "NC_20") (pintype "no_connect"))
    )
  )
)
